# ATTiny2312_ISPProgrammer.net
KiCad netlist of a schematic drawn in EAGLE
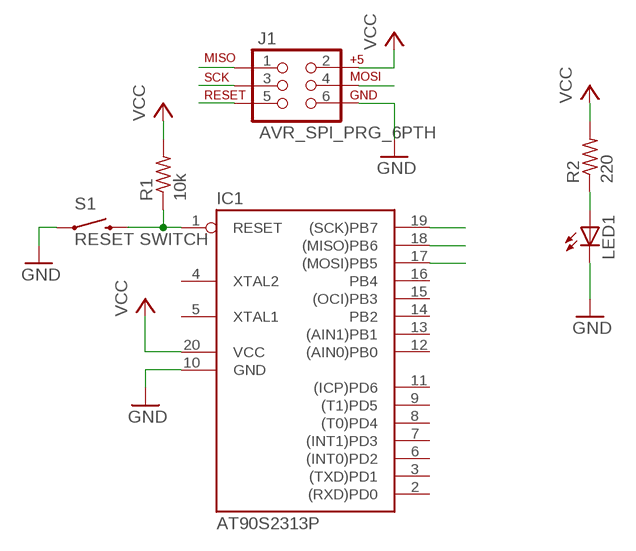
[diagram p0: schematic, sheet 1]

(export (version "E")
  (design (tool "Eeschema 10.0.6"))
  (components
    (comp (ref "IC1")
      (value "AT90S2313P")
      (footprint "eagle-import:DIL20")
      (libsource (lib "eagle-import") (part "AT90S2313P"))
    )
    (comp (ref "J1")
      (value "AVR_SPI_PRG_6PTH")
      (footprint "eagle-import:2X3")
      (libsource (lib "eagle-import") (part "AVR_SPI_PRG_6PTH"))
    )
    (comp (ref "LED1")
      (value "LED-3MM-NO_SILK")
      (footprint "eagle-import:LED3MM-NS")
      (libsource (lib "eagle-import") (part "LED-3MM-NO_SILK"))
    )
    (comp (ref "R1")
      (value "10k")
      (footprint "eagle-import:0207_10")
      (libsource (lib "eagle-import") (part "R-US_0207/10"))
    )
    (comp (ref "R2")
      (value "220")
      (footprint "eagle-import:0207_10")
      (libsource (lib "eagle-import") (part "R-US_0207/10"))
    )
    (comp (ref "S1")
      (value "RESET SWITCH")
      (footprint "eagle-import:TACTILE-PTH")
      (libsource (lib "eagle-import") (part "SWITCH-MOMENTARY-2PTH"))
    )
  )
  (nets
    (net (code "1") (name "/MISO") (class "Default")
      (node (ref "IC1") (pin "18") (pinfunction "(MISO)PB6_18") (pintype "bidirectional"))
      (node (ref "J1") (pin "1") (pinfunction "1_1") (pintype "passive"))
    )
    (net (code "2") (name "/MOSI") (class "Default")
      (node (ref "IC1") (pin "17") (pinfunction "(MOSI)PB5_17") (pintype "bidirectional"))
      (node (ref "J1") (pin "4") (pinfunction "4_4") (pintype "passive"))
    )
    (net (code "3") (name "/RST") (class "Default")
      (node (ref "IC1") (pin "1") (pinfunction "RESET_1") (pintype "bidirectional"))
      (node (ref "J1") (pin "5") (pinfunction "5_5") (pintype "passive"))
      (node (ref "R1") (pin "1") (pinfunction "1_1") (pintype "passive"))
      (node (ref "S1") (pin "3") (pinfunction "2_3") (pintype "passive"))
    )
    (net (code "4") (name "/SCK") (class "Default")
      (node (ref "IC1") (pin "19") (pinfunction "(SCK)PB7_19") (pintype "bidirectional"))
      (node (ref "J1") (pin "3") (pinfunction "3_3") (pintype "passive"))
    )
    (net (code "5") (name "GND") (class "Default")
      (node (ref "IC1") (pin "10") (pinfunction "GND_10") (pintype "power_in"))
      (node (ref "J1") (pin "6") (pinfunction "6_6") (pintype "passive"))
      (node (ref "LED1") (pin "K") (pinfunction "C_K") (pintype "passive"))
      (node (ref "S1") (pin "1") (pinfunction "1_1") (pintype "passive"))
    )
    (net (code "6") (name "Net-(LED1-PadA)") (class "Default")
      (node (ref "LED1") (pin "A") (pinfunction "A_A") (pintype "passive"))
      (node (ref "R2") (pin "1") (pinfunction "1_1") (pintype "passive"))
    )
    (net (code "7") (name "VCC") (class "Default")
      (node (ref "IC1") (pin "20") (pinfunction "VCC_20") (pintype "power_in"))
      (node (ref "J1") (pin "2") (pinfunction "2_2") (pintype "passive"))
      (node (ref "R1") (pin "2") (pinfunction "2_2") (pintype "passive"))
      (node (ref "R2") (pin "2") (pinfunction "2_2") (pintype "passive"))
    )
    (net (code "8") (name "unconnected-(IC1-(AIN0)PB0-Pad12)") (class "Default")
      (node (ref "IC1") (pin "12") (pinfunction "(AIN0)PB0_12") (pintype "bidirectional"))
    )
    (net (code "9") (name "unconnected-(IC1-(AIN1)PB1-Pad13)") (class "Default")
      (node (ref "IC1") (pin "13") (pinfunction "(AIN1)PB1_13") (pintype "bidirectional"))
    )
    (net (code "10") (name "unconnected-(IC1-(ICP)PD6-Pad11)") (class "Default")
      (node (ref "IC1") (pin "11") (pinfunction "(ICP)PD6_11") (pintype "bidirectional"))
    )
    (net (code "11") (name "unconnected-(IC1-(INT0)PD2-Pad6)") (class "Default")
      (node (ref "IC1") (pin "6") (pinfunction "(INT0)PD2_6") (pintype "bidirectional"))
    )
    (net (code "12") (name "unconnected-(IC1-(INT1)PD3-Pad7)") (class "Default")
      (node (ref "IC1") (pin "7") (pinfunction "(INT1)PD3_7") (pintype "bidirectional"))
    )
    (net (code "13") (name "unconnected-(IC1-(OCI)PB3-Pad15)") (class "Default")
      (node (ref "IC1") (pin "15") (pinfunction "(OCI)PB3_15") (pintype "bidirectional"))
    )
    (net (code "14") (name "unconnected-(IC1-(RXD)PD0-Pad2)") (class "Default")
      (node (ref "IC1") (pin "2") (pinfunction "(RXD)PD0_2") (pintype "bidirectional"))
    )
    (net (code "15") (name "unconnected-(IC1-(T0)PD4-Pad8)") (class "Default")
      (node (ref "IC1") (pin "8") (pinfunction "(T0)PD4_8") (pintype "bidirectional"))
    )
    (net (code "16") (name "unconnected-(IC1-(T1)PD5-Pad9)") (class "Default")
      (node (ref "IC1") (pin "9") (pinfunction "(T1)PD5_9") (pintype "bidirectional"))
    )
    (net (code "17") (name "unconnected-(IC1-(TXD)PD1-Pad3)") (class "Default")
      (node (ref "IC1") (pin "3") (pinfunction "(TXD)PD1_3") (pintype "bidirectional"))
    )
    (net (code "18") (name "unconnected-(IC1-PB2-Pad14)") (class "Default")
      (node (ref "IC1") (pin "14") (pinfunction "PB2_14") (pintype "bidirectional"))
    )
    (net (code "19") (name "unconnected-(IC1-PB4-Pad16)") (class "Default")
      (node (ref "IC1") (pin "16") (pinfunction "PB4_16") (pintype "bidirectional"))
    )
    (net (code "20") (name "unconnected-(IC1-XTAL1-Pad5)") (class "Default")
      (node (ref "IC1") (pin "5") (pinfunction "XTAL1_5") (pintype "bidirectional"))
    )
    (net (code "21") (name "unconnected-(IC1-XTAL2-Pad4)") (class "Default")
      (node (ref "IC1") (pin "4") (pinfunction "XTAL2_4") (pintype "bidirectional"))
    )
  )
)
